# hat.net
KiCad netlist of a schematic drawn in Altium Designer
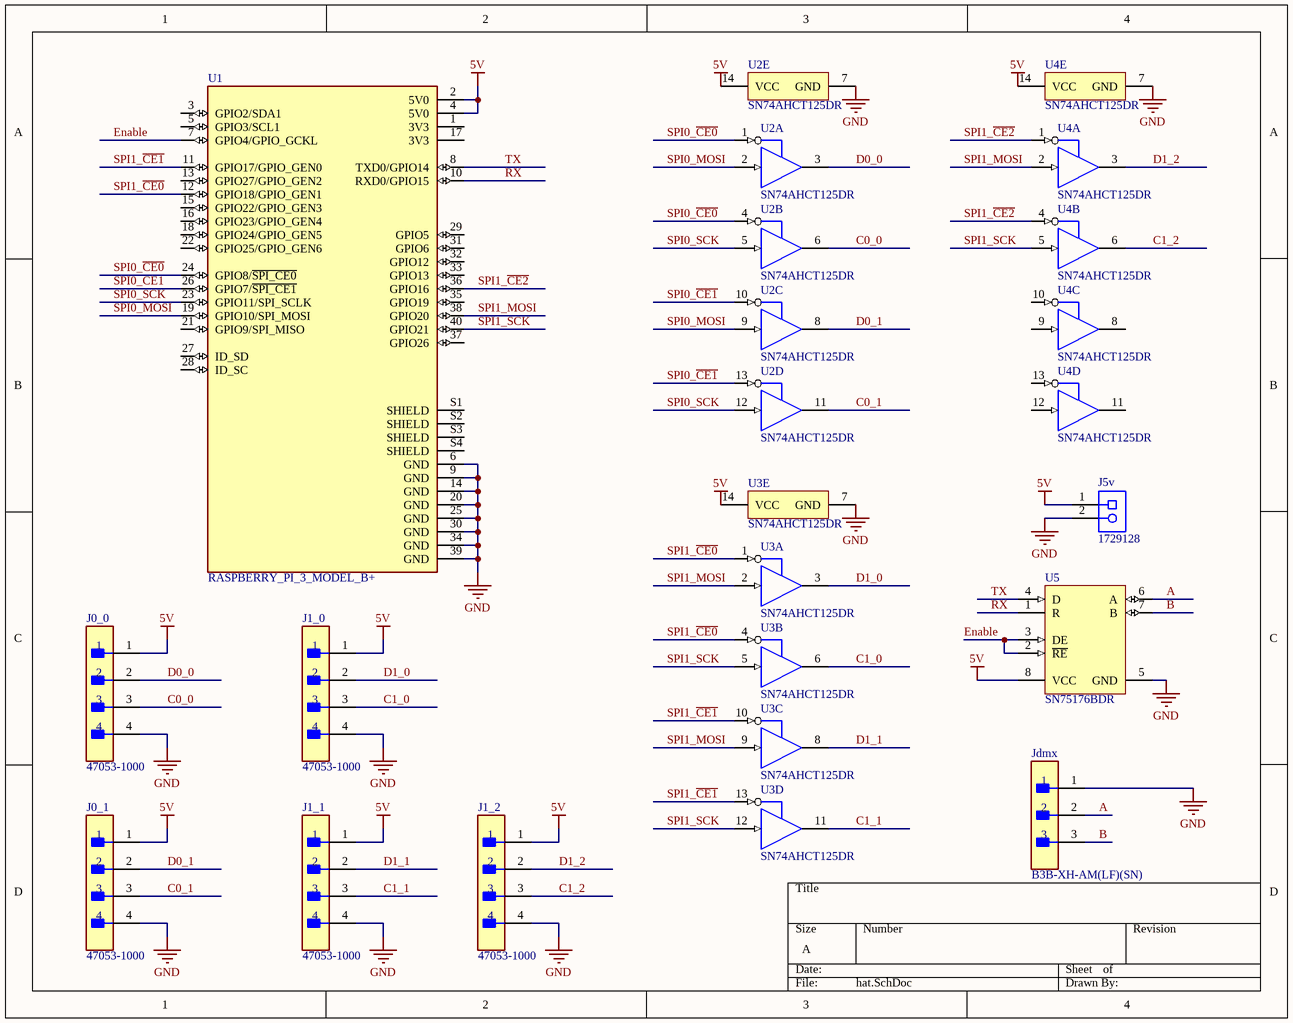
[diagram p0: hat.SchDoc]

(export (version "E")
  (design (tool "Eeschema 10.0.6"))
  (components
    (comp (ref "J0_0")
      (value "47053-1000")
      (footprint "FP-47053-1000-MFG")
      (description "CONN HEADER VERT 4POS 2.54MM")
      (libsource (lib "Altium Content Vault") (part "299a8cea1bdcbc3624fe62c390fa72c"))
    )
    (comp (ref "J0_1")
      (value "47053-1000")
      (footprint "FP-47053-1000-MFG")
      (description "CONN HEADER VERT 4POS 2.54MM")
      (libsource (lib "Altium Content Vault") (part "299a8cea1bdcbc3624fe62c390fa72c"))
    )
    (comp (ref "J1_0")
      (value "47053-1000")
      (footprint "FP-47053-1000-MFG")
      (description "CONN HEADER VERT 4POS 2.54MM")
      (libsource (lib "Altium Content Vault") (part "299a8cea1bdcbc3624fe62c390fa72c"))
    )
    (comp (ref "J1_1")
      (value "47053-1000")
      (footprint "FP-47053-1000-MFG")
      (description "CONN HEADER VERT 4POS 2.54MM")
      (libsource (lib "Altium Content Vault") (part "299a8cea1bdcbc3624fe62c390fa72c"))
    )
    (comp (ref "J1_2")
      (value "47053-1000")
      (footprint "FP-47053-1000-MFG")
      (description "CONN HEADER VERT 4POS 2.54MM")
      (libsource (lib "Altium Content Vault") (part "299a8cea1bdcbc3624fe62c390fa72c"))
    )
    (comp (ref "J5v")
      (value "1729128")
      (footprint "PHOE-1729128-2_V")
      (description "PCB Terminal Block, 13.5 A, 400 V, 2-Pin THD, RoHS, Bulk")
      (fields (field (name "MANUFACTURER") "Phoenix Contact"))
      (libsource (lib "Altium Content Vault") (part "CN-2P-F-R2"))
    )
    (comp (ref "Jdmx")
      (value "B3B-XH-AM(LF)(SN)")
      (footprint "FP-B3B-XH-AM_LF_SN-MFG")
      (description "CONN HEADER VERT 3POS 2.5MM")
      (libsource (lib "Altium Content Vault") (part "0d3f023dd272f625e17a2be33dea85f"))
    )
    (comp (ref "U1")
      (value "RASPBERRY_PI_3_MODEL_B+")
      (footprint "MODULE_RASPBERRY_PI_3_MODEL_B+")
      (description "BCM2835 Raspberry Pi Model B+ - ARM11, VideoCore MPU Embedded Evaluation Board")
      (libsource (lib "RASPBERRY_PI_3_MODEL_B_") (part "RASPBERRY_PI_3_MODEL_B+"))
    )
    (comp (ref "U2")
      (value "SN74AHCT125DR")
      (footprint "D0014A_N")
      (description "Quadruple Bus Buffer Gates With 3-State Outputs, D0014A, LARGE T&R")
      (fields
        (field (name "MANUFACTURER") "Texas Instruments")
        (field (name "GENERIC PART NUMBER") "SN74AHCT125")
      )
      (libsource (lib "Altium Content Vault") (part "TI-SN74AHCT125-D0014A-14"))
    )
    (comp (ref "U3")
      (value "SN74AHCT125DR")
      (footprint "D0014A_N")
      (description "Quadruple Bus Buffer Gates With 3-State Outputs, D0014A, LARGE T&R")
      (fields
        (field (name "MANUFACTURER") "Texas Instruments")
        (field (name "GENERIC PART NUMBER") "SN74AHCT125")
      )
      (libsource (lib "Altium Content Vault") (part "TI-SN74AHCT125-D0014A-14"))
    )
    (comp (ref "U4")
      (value "SN74AHCT125DR")
      (footprint "D0014A_N")
      (description "Quadruple Bus Buffer Gates With 3-State Outputs, D0014A, LARGE T&R")
      (fields
        (field (name "MANUFACTURER") "Texas Instruments")
        (field (name "GENERIC PART NUMBER") "SN74AHCT125")
      )
      (libsource (lib "Altium Content Vault") (part "TI-SN74AHCT125-D0014A-14"))
    )
    (comp (ref "U5")
      (value "SN75176BDR")
      (footprint "D0008A_M")
      (fields (field (name "MANUFACTURER") "Texas Instruments"))
      (libsource (lib "Altium Content Vault") (part "TI-SN75176B-SOIC_D-8"))
    )
  )
  (nets
    (net (code "1") (name "/A") (class "Default")
      (node (ref "Jdmx") (pin "2") (pinfunction "2_2") (pintype "passive"))
      (node (ref "U5") (pin "6") (pinfunction "A_6") (pintype "bidirectional"))
    )
    (net (code "2") (name "/B") (class "Default")
      (node (ref "Jdmx") (pin "3") (pinfunction "3_3") (pintype "passive"))
      (node (ref "U5") (pin "7") (pinfunction "B_7") (pintype "bidirectional"))
    )
    (net (code "3") (name "/C0_0") (class "Default")
      (node (ref "J0_0") (pin "3") (pinfunction "3_3") (pintype "passive"))
      (node (ref "U2") (pin "6") (pinfunction "2Y_6") (pintype "tri_state"))
    )
    (net (code "4") (name "/C0_1") (class "Default")
      (node (ref "J0_1") (pin "3") (pinfunction "3_3") (pintype "passive"))
      (node (ref "U2") (pin "11") (pinfunction "4Y_11") (pintype "tri_state"))
    )
    (net (code "5") (name "/C1_0") (class "Default")
      (node (ref "J1_0") (pin "3") (pinfunction "3_3") (pintype "passive"))
      (node (ref "U3") (pin "6") (pinfunction "2Y_6") (pintype "tri_state"))
    )
    (net (code "6") (name "/C1_1") (class "Default")
      (node (ref "J1_1") (pin "3") (pinfunction "3_3") (pintype "passive"))
      (node (ref "U3") (pin "11") (pinfunction "4Y_11") (pintype "tri_state"))
    )
    (net (code "7") (name "/C1_2") (class "Default")
      (node (ref "J1_2") (pin "3") (pinfunction "3_3") (pintype "passive"))
      (node (ref "U4") (pin "6") (pinfunction "2Y_6") (pintype "tri_state"))
    )
    (net (code "8") (name "/D0_0") (class "Default")
      (node (ref "J0_0") (pin "2") (pinfunction "2_2") (pintype "passive"))
      (node (ref "U2") (pin "3") (pinfunction "1Y_3") (pintype "tri_state"))
    )
    (net (code "9") (name "/D0_1") (class "Default")
      (node (ref "J0_1") (pin "2") (pinfunction "2_2") (pintype "passive"))
      (node (ref "U2") (pin "8") (pinfunction "3Y_8") (pintype "tri_state"))
    )
    (net (code "10") (name "/D1_0") (class "Default")
      (node (ref "J1_0") (pin "2") (pinfunction "2_2") (pintype "passive"))
      (node (ref "U3") (pin "3") (pinfunction "1Y_3") (pintype "tri_state"))
    )
    (net (code "11") (name "/D1_1") (class "Default")
      (node (ref "J1_1") (pin "2") (pinfunction "2_2") (pintype "passive"))
      (node (ref "U3") (pin "8") (pinfunction "3Y_8") (pintype "tri_state"))
    )
    (net (code "12") (name "/D1_2") (class "Default")
      (node (ref "J1_2") (pin "2") (pinfunction "2_2") (pintype "passive"))
      (node (ref "U4") (pin "3") (pinfunction "1Y_3") (pintype "tri_state"))
    )
    (net (code "13") (name "/Enable") (class "Default")
      (node (ref "U1") (pin "7") (pinfunction "GPIO4/GPIO_GCKL_7") (pintype "bidirectional"))
      (node (ref "U5") (pin "2") (pinfunction "~{RE}_2") (pintype "input"))
      (node (ref "U5") (pin "3") (pinfunction "DE_3") (pintype "input"))
    )
    (net (code "14") (name "/RX") (class "Default")
      (node (ref "U1") (pin "10") (pinfunction "RXD0/GPIO15_10") (pintype "bidirectional"))
      (node (ref "U5") (pin "1") (pinfunction "R_1") (pintype "tri_state"))
    )
    (net (code "15") (name "/SPI0_MOSI") (class "Default")
      (node (ref "U1") (pin "19") (pinfunction "GPIO10/SPI_MOSI_19") (pintype "bidirectional"))
      (node (ref "U2") (pin "2") (pinfunction "1A_2") (pintype "input"))
      (node (ref "U2") (pin "9") (pinfunction "3A_9") (pintype "input"))
    )
    (net (code "16") (name "/SPI0_SCK") (class "Default")
      (node (ref "U1") (pin "23") (pinfunction "GPIO11/SPI_SCLK_23") (pintype "bidirectional"))
      (node (ref "U2") (pin "12") (pinfunction "4A_12") (pintype "input"))
      (node (ref "U2") (pin "5") (pinfunction "2A_5") (pintype "input"))
    )
    (net (code "17") (name "/SPI0_~{CE0}") (class "Default")
      (node (ref "U1") (pin "24") (pinfunction "GPIO8/~{SPI_CE0}_24") (pintype "bidirectional"))
      (node (ref "U2") (pin "1") (pinfunction "1~{OE}_1") (pintype "input"))
      (node (ref "U2") (pin "4") (pinfunction "2~{OE}_4") (pintype "input"))
    )
    (net (code "18") (name "/SPI0_~{CE1}") (class "Default")
      (node (ref "U1") (pin "26") (pinfunction "GPIO7/~{SPI_CE1}_26") (pintype "bidirectional"))
      (node (ref "U2") (pin "10") (pinfunction "3~{OE}_10") (pintype "input"))
      (node (ref "U2") (pin "13") (pinfunction "4~{OE}_13") (pintype "input"))
    )
    (net (code "19") (name "/SPI1_MOSI") (class "Default")
      (node (ref "U1") (pin "38") (pinfunction "GPIO20_38") (pintype "bidirectional"))
      (node (ref "U3") (pin "2") (pinfunction "1A_2") (pintype "input"))
      (node (ref "U3") (pin "9") (pinfunction "3A_9") (pintype "input"))
      (node (ref "U4") (pin "2") (pinfunction "1A_2") (pintype "input"))
    )
    (net (code "20") (name "/SPI1_SCK") (class "Default")
      (node (ref "U1") (pin "40") (pinfunction "GPIO21_40") (pintype "bidirectional"))
      (node (ref "U3") (pin "12") (pinfunction "4A_12") (pintype "input"))
      (node (ref "U3") (pin "5") (pinfunction "2A_5") (pintype "input"))
      (node (ref "U4") (pin "5") (pinfunction "2A_5") (pintype "input"))
    )
    (net (code "21") (name "/SPI1_~{CE0}") (class "Default")
      (node (ref "U1") (pin "12") (pinfunction "GPIO18/GPIO_GEN1_12") (pintype "bidirectional"))
      (node (ref "U3") (pin "1") (pinfunction "1~{OE}_1") (pintype "input"))
      (node (ref "U3") (pin "4") (pinfunction "2~{OE}_4") (pintype "input"))
    )
    (net (code "22") (name "/SPI1_~{CE1}") (class "Default")
      (node (ref "U1") (pin "11") (pinfunction "GPIO17/GPIO_GEN0_11") (pintype "bidirectional"))
      (node (ref "U3") (pin "10") (pinfunction "3~{OE}_10") (pintype "input"))
      (node (ref "U3") (pin "13") (pinfunction "4~{OE}_13") (pintype "input"))
    )
    (net (code "23") (name "/SPI1_~{CE2}") (class "Default")
      (node (ref "U1") (pin "36") (pinfunction "GPIO16_36") (pintype "bidirectional"))
      (node (ref "U4") (pin "1") (pinfunction "1~{OE}_1") (pintype "input"))
      (node (ref "U4") (pin "4") (pinfunction "2~{OE}_4") (pintype "input"))
    )
    (net (code "24") (name "/TX") (class "Default")
      (node (ref "U1") (pin "8") (pinfunction "TXD0/GPIO14_8") (pintype "bidirectional"))
      (node (ref "U5") (pin "4") (pinfunction "D_4") (pintype "input"))
    )
    (net (code "25") (name "5V") (class "Default")
      (node (ref "J0_0") (pin "1") (pinfunction "1_1") (pintype "passive"))
      (node (ref "J0_1") (pin "1") (pinfunction "1_1") (pintype "passive"))
      (node (ref "J1_0") (pin "1") (pinfunction "1_1") (pintype "passive"))
      (node (ref "J1_1") (pin "1") (pinfunction "1_1") (pintype "passive"))
      (node (ref "J1_2") (pin "1") (pinfunction "1_1") (pintype "passive"))
      (node (ref "J5v") (pin "1") (pinfunction "1_1") (pintype "passive"))
      (node (ref "U1") (pin "2") (pinfunction "5V0_2") (pintype "power_in"))
      (node (ref "U1") (pin "4") (pinfunction "5V0_4") (pintype "power_in"))
      (node (ref "U2") (pin "14") (pinfunction "VCC_14") (pintype "power_in"))
      (node (ref "U3") (pin "14") (pinfunction "VCC_14") (pintype "power_in"))
      (node (ref "U4") (pin "14") (pinfunction "VCC_14") (pintype "power_in"))
      (node (ref "U5") (pin "8") (pinfunction "VCC_8") (pintype "power_in"))
    )
    (net (code "26") (name "GND") (class "Default")
      (node (ref "J0_0") (pin "4") (pinfunction "4_4") (pintype "passive"))
      (node (ref "J0_1") (pin "4") (pinfunction "4_4") (pintype "passive"))
      (node (ref "J1_0") (pin "4") (pinfunction "4_4") (pintype "passive"))
      (node (ref "J1_1") (pin "4") (pinfunction "4_4") (pintype "passive"))
      (node (ref "J1_2") (pin "4") (pinfunction "4_4") (pintype "passive"))
      (node (ref "J5v") (pin "2") (pinfunction "2_2") (pintype "passive"))
      (node (ref "Jdmx") (pin "1") (pinfunction "1_1") (pintype "passive"))
      (node (ref "U1") (pin "14") (pinfunction "GND_14") (pintype "power_in"))
      (node (ref "U1") (pin "20") (pinfunction "GND_20") (pintype "power_in"))
      (node (ref "U1") (pin "25") (pinfunction "GND_25") (pintype "power_in"))
      (node (ref "U1") (pin "30") (pinfunction "GND_30") (pintype "power_in"))
      (node (ref "U1") (pin "34") (pinfunction "GND_34") (pintype "power_in"))
      (node (ref "U1") (pin "39") (pinfunction "GND_39") (pintype "power_in"))
      (node (ref "U1") (pin "6") (pinfunction "GND_6") (pintype "power_in"))
      (node (ref "U1") (pin "9") (pinfunction "GND_9") (pintype "power_in"))
      (node (ref "U2") (pin "7") (pinfunction "GND_7") (pintype "power_in"))
      (node (ref "U3") (pin "7") (pinfunction "GND_7") (pintype "power_in"))
      (node (ref "U4") (pin "7") (pinfunction "GND_7") (pintype "power_in"))
      (node (ref "U5") (pin "5") (pinfunction "GND_5") (pintype "power_in"))
    )
    (net (code "27") (name "unconnected-(U1-3V3-Pad1)") (class "Default")
      (node (ref "U1") (pin "1") (pinfunction "3V3_1") (pintype "power_in"))
    )
    (net (code "28") (name "unconnected-(U1-3V3-Pad17)") (class "Default")
      (node (ref "U1") (pin "17") (pinfunction "3V3_17") (pintype "power_in"))
    )
    (net (code "29") (name "unconnected-(U1-GPIO2{slash}SDA1-Pad3)") (class "Default")
      (node (ref "U1") (pin "3") (pinfunction "GPIO2/SDA1_3") (pintype "bidirectional"))
    )
    (net (code "30") (name "unconnected-(U1-GPIO3{slash}SCL1-Pad5)") (class "Default")
      (node (ref "U1") (pin "5") (pinfunction "GPIO3/SCL1_5") (pintype "bidirectional"))
    )
    (net (code "31") (name "unconnected-(U1-GPIO5-Pad29)") (class "Default")
      (node (ref "U1") (pin "29") (pinfunction "GPIO5_29") (pintype "bidirectional"))
    )
    (net (code "32") (name "unconnected-(U1-GPIO6-Pad31)") (class "Default")
      (node (ref "U1") (pin "31") (pinfunction "GPIO6_31") (pintype "bidirectional"))
    )
    (net (code "33") (name "unconnected-(U1-GPIO9{slash}SPI_MISO-Pad21)") (class "Default")
      (node (ref "U1") (pin "21") (pinfunction "GPIO9/SPI_MISO_21") (pintype "bidirectional"))
    )
    (net (code "34") (name "unconnected-(U1-GPIO12-Pad32)") (class "Default")
      (node (ref "U1") (pin "32") (pinfunction "GPIO12_32") (pintype "bidirectional"))
    )
    (net (code "35") (name "unconnected-(U1-GPIO13-Pad33)") (class "Default")
      (node (ref "U1") (pin "33") (pinfunction "GPIO13_33") (pintype "bidirectional"))
    )
    (net (code "36") (name "unconnected-(U1-GPIO19-Pad35)") (class "Default")
      (node (ref "U1") (pin "35") (pinfunction "GPIO19_35") (pintype "bidirectional"))
    )
    (net (code "37") (name "unconnected-(U1-GPIO22{slash}GPIO_GEN3-Pad15)") (class "Default")
      (node (ref "U1") (pin "15") (pinfunction "GPIO22/GPIO_GEN3_15") (pintype "bidirectional"))
    )
    (net (code "38") (name "unconnected-(U1-GPIO23{slash}GPIO_GEN4-Pad16)") (class "Default")
      (node (ref "U1") (pin "16") (pinfunction "GPIO23/GPIO_GEN4_16") (pintype "bidirectional"))
    )
    (net (code "39") (name "unconnected-(U1-GPIO24{slash}GPIO_GEN5-Pad18)") (class "Default")
      (node (ref "U1") (pin "18") (pinfunction "GPIO24/GPIO_GEN5_18") (pintype "bidirectional"))
    )
    (net (code "40") (name "unconnected-(U1-GPIO25{slash}GPIO_GEN6-Pad22)") (class "Default")
      (node (ref "U1") (pin "22") (pinfunction "GPIO25/GPIO_GEN6_22") (pintype "bidirectional"))
    )
    (net (code "41") (name "unconnected-(U1-GPIO26-Pad37)") (class "Default")
      (node (ref "U1") (pin "37") (pinfunction "GPIO26_37") (pintype "bidirectional"))
    )
    (net (code "42") (name "unconnected-(U1-GPIO27{slash}GPIO_GEN2-Pad13)") (class "Default")
      (node (ref "U1") (pin "13") (pinfunction "GPIO27/GPIO_GEN2_13") (pintype "bidirectional"))
    )
    (net (code "43") (name "unconnected-(U1-ID_SC-Pad28)") (class "Default")
      (node (ref "U1") (pin "28") (pinfunction "ID_SC_28") (pintype "bidirectional"))
    )
    (net (code "44") (name "unconnected-(U1-ID_SD-Pad27)") (class "Default")
      (node (ref "U1") (pin "27") (pinfunction "ID_SD_27") (pintype "bidirectional"))
    )
    (net (code "45") (name "unconnected-(U1-SHIELD-PadS1)") (class "Default")
      (node (ref "U1") (pin "S1") (pinfunction "SHIELD_S1") (pintype "power_in"))
    )
    (net (code "46") (name "unconnected-(U1-SHIELD-PadS2)") (class "Default")
      (node (ref "U1") (pin "S2") (pinfunction "SHIELD_S2") (pintype "power_in"))
    )
    (net (code "47") (name "unconnected-(U1-SHIELD-PadS3)") (class "Default")
      (node (ref "U1") (pin "S3") (pinfunction "SHIELD_S3") (pintype "power_in"))
    )
    (net (code "48") (name "unconnected-(U1-SHIELD-PadS4)") (class "Default")
      (node (ref "U1") (pin "S4") (pinfunction "SHIELD_S4") (pintype "power_in"))
    )
    (net (code "49") (name "unconnected-(U4C-3A-Pad9)") (class "Default")
      (node (ref "U4") (pin "9") (pinfunction "3A_9") (pintype "input"))
    )
    (net (code "50") (name "unconnected-(U4C-3Y-Pad8)") (class "Default")
      (node (ref "U4") (pin "8") (pinfunction "3Y_8") (pintype "tri_state"))
    )
    (net (code "51") (name "unconnected-(U4C-3~{OE}-Pad10)") (class "Default")
      (node (ref "U4") (pin "10") (pinfunction "3~{OE}_10") (pintype "input"))
    )
    (net (code "52") (name "unconnected-(U4D-4A-Pad12)") (class "Default")
      (node (ref "U4") (pin "12") (pinfunction "4A_12") (pintype "input"))
    )
    (net (code "53") (name "unconnected-(U4D-4Y-Pad11)") (class "Default")
      (node (ref "U4") (pin "11") (pinfunction "4Y_11") (pintype "tri_state"))
    )
    (net (code "54") (name "unconnected-(U4D-4~{OE}-Pad13)") (class "Default")
      (node (ref "U4") (pin "13") (pinfunction "4~{OE}_13") (pintype "input"))
    )
  )
)
